# Page11_BOOT_CFG.net
KiCad netlist of a schematic drawn in Altium Designer
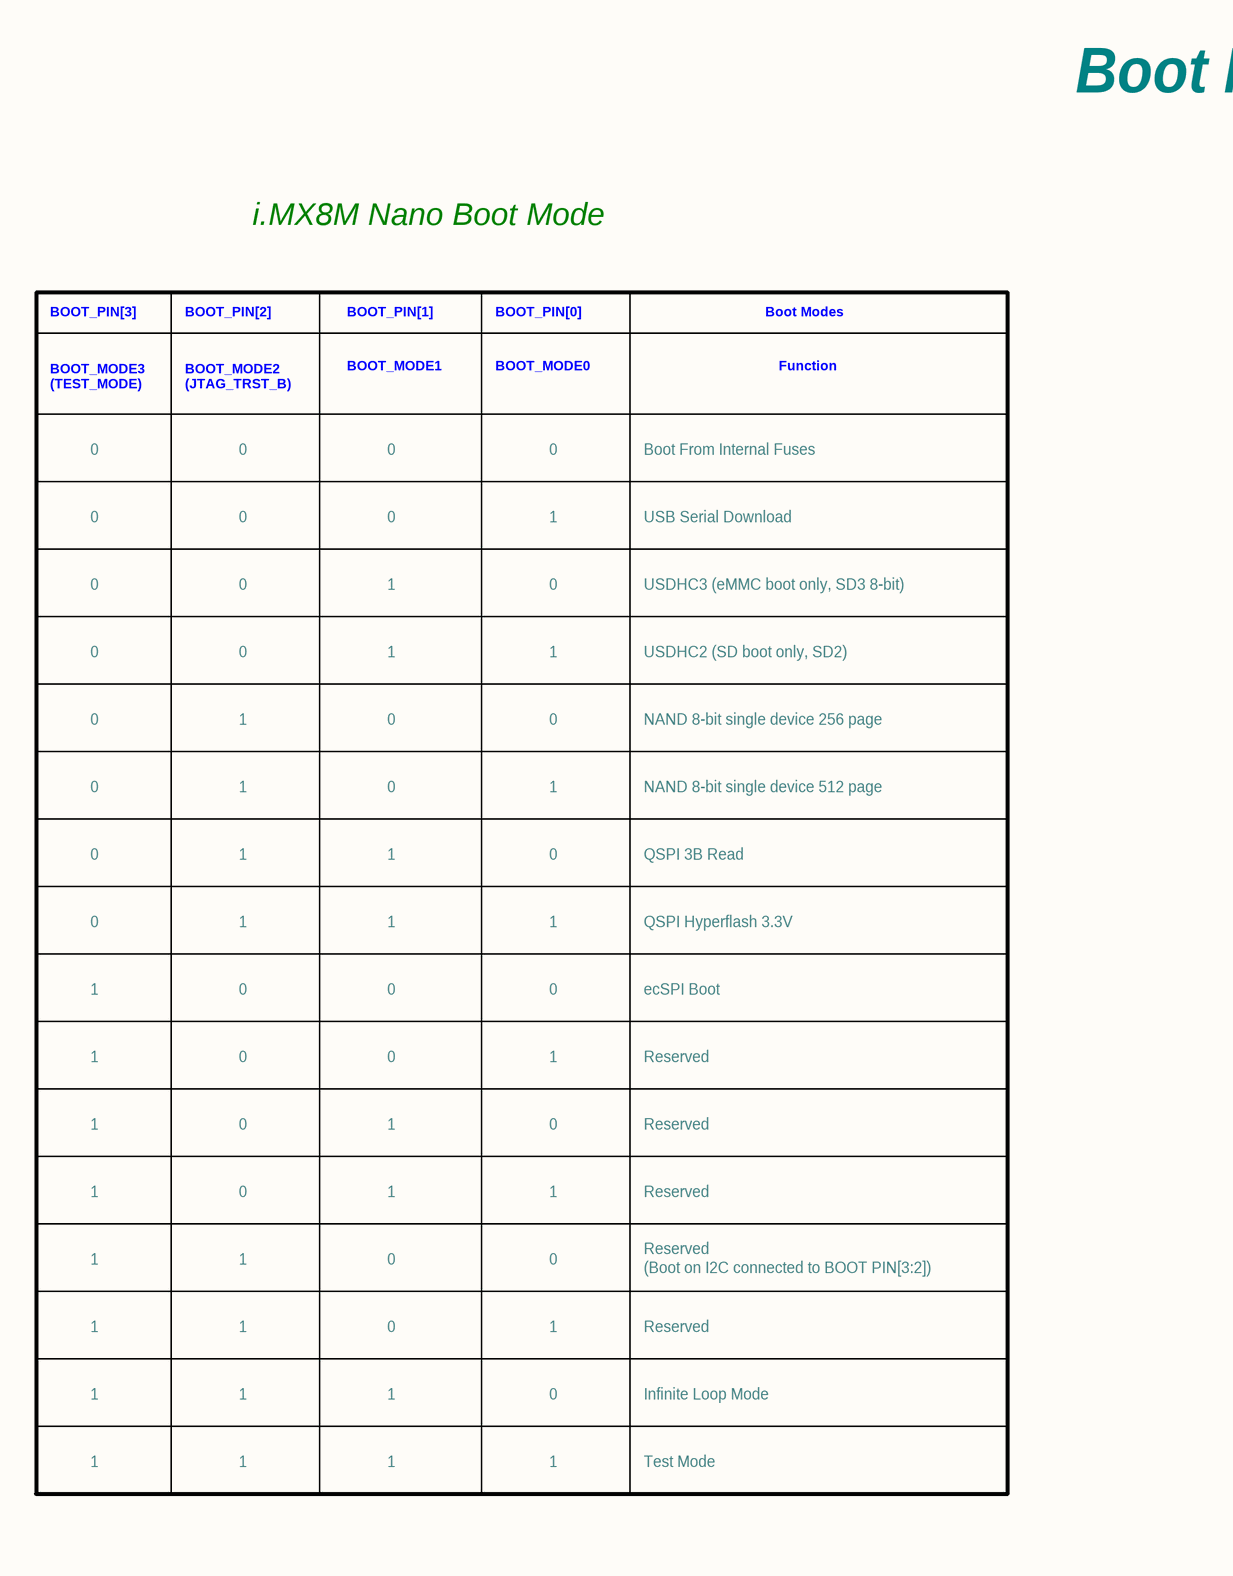
[diagram p0: Page11 BOOT_CFG.SchDoc, left]
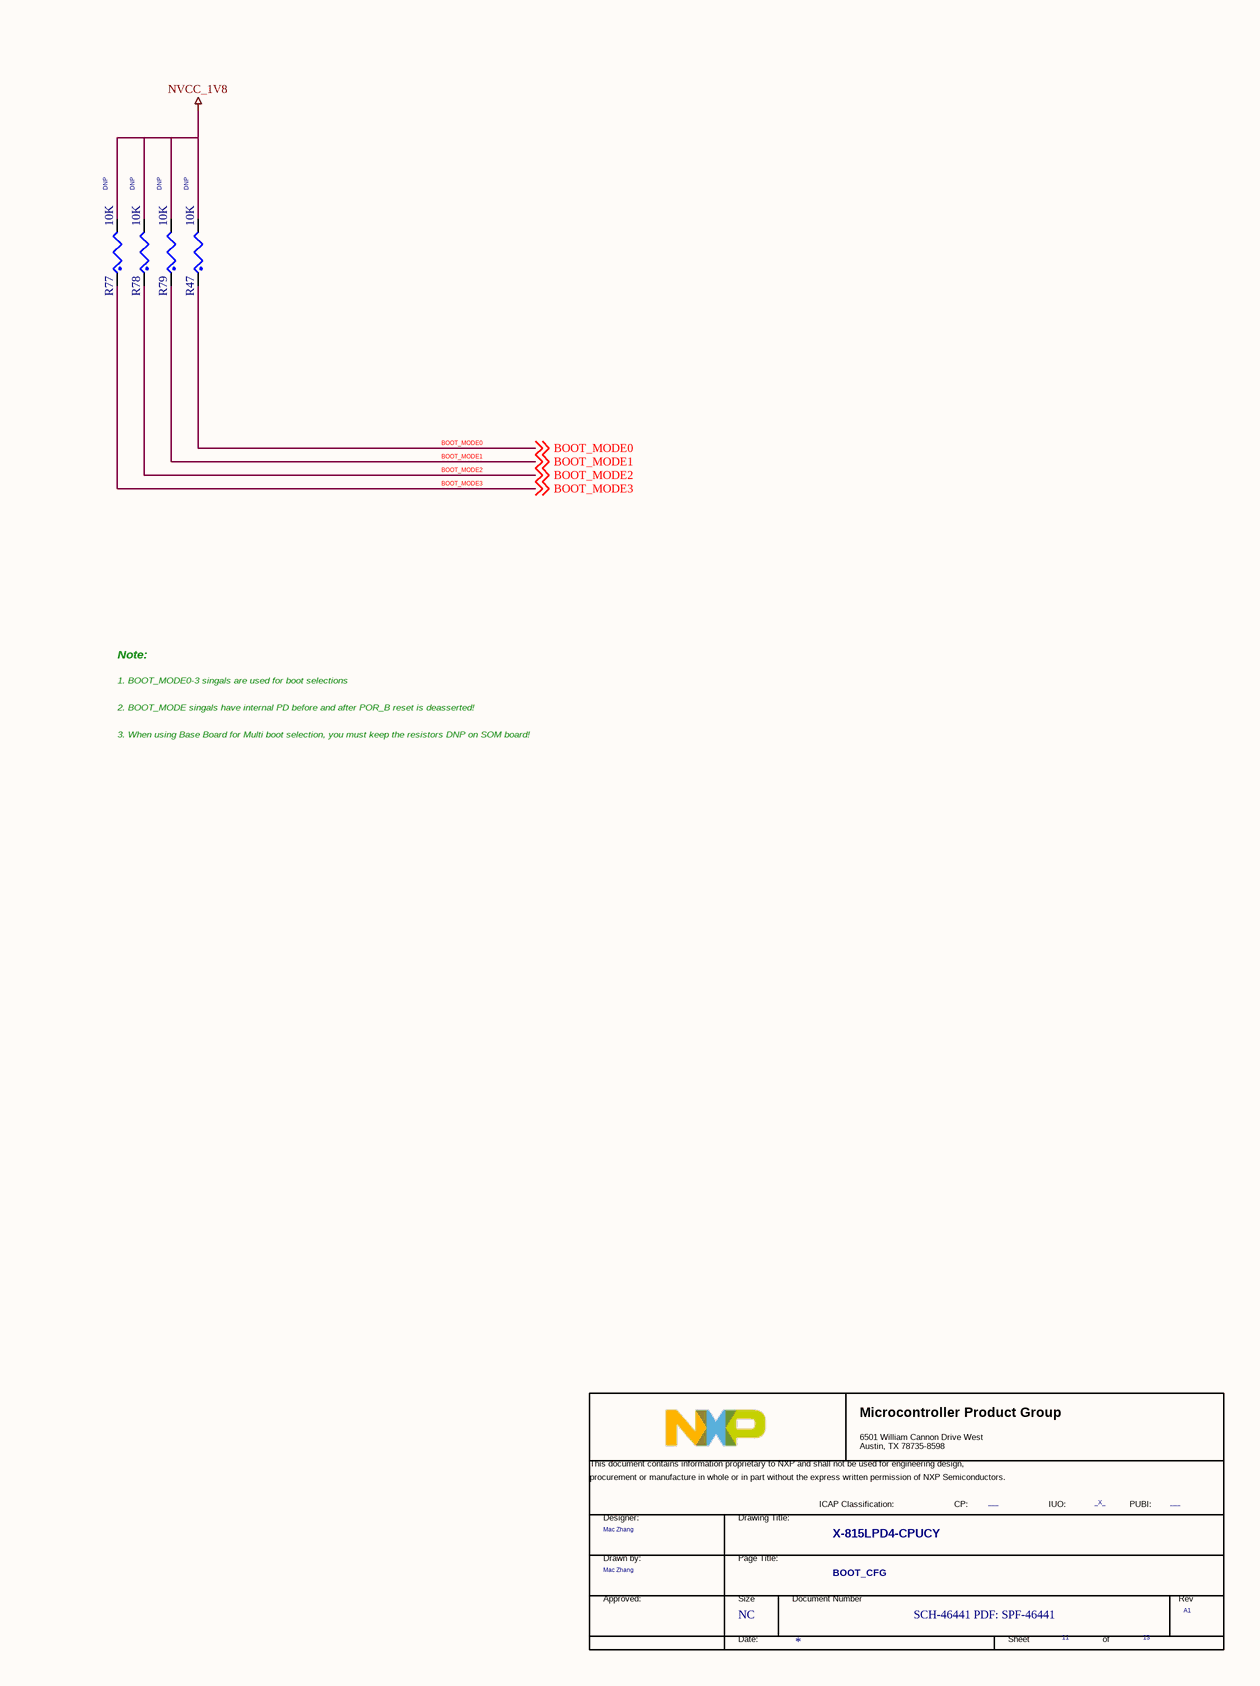
[diagram p1: Page11 BOOT_CFG.SchDoc, right]

(export (version "E")
  (design (tool "Eeschema 10.0.6"))
  (components
    (comp (ref "*")
      (value "TitleBlock_MCPG")
      (fields
        (field (name "DOC") "SCH-46441 PDF: SPF-46441")
        (field (name "REVCODE") "A1")
        (field (name "TITLE") "X-815LPD4-CPUCY")
        (field (name "PAGE SIZE") "NC")
        (field (name "PAGE NUMBER") "11")
        (field (name "PAGE COUNT") "13")
        (field (name "PAGETITLE") "BOOT_CFG")
        (field (name "DESIGNER") "Mac Zhang")
        (field (name "DRAWNBY") "Mac Zhang")
        (field (name "PUBI") "___")
        (field (name "FIUO") "_X_")
        (field (name "FCP") "___")
      )
      (libsource (lib "*") (part "TitleBlock_MCPG"))
    )
    (comp (ref "R47")
      (value "10K")
      (footprint "0402_CC")
      (description "RES MF 10K 1/16W 5% 0402")
      (fields (field (name "ASSY_OPT") "DNP") (field (name "TOLERANCE") "5%"))
      (libsource (lib "*") (part "RES"))
    )
    (comp (ref "R77")
      (value "10K")
      (footprint "0402_CC")
      (description "RES MF 10K 1/16W 5% 0402")
      (fields (field (name "ASSY_OPT") "DNP") (field (name "TOLERANCE") "5%"))
      (libsource (lib "*") (part "RES"))
    )
    (comp (ref "R78")
      (value "10K")
      (footprint "0402_CC")
      (description "RES MF 10K 1/16W 5% 0402")
      (fields (field (name "ASSY_OPT") "DNP") (field (name "TOLERANCE") "5%"))
      (libsource (lib "*") (part "RES"))
    )
    (comp (ref "R79")
      (value "10K")
      (footprint "0402_CC")
      (description "RES MF 10K 1/16W 5% 0402")
      (fields (field (name "ASSY_OPT") "DNP") (field (name "TOLERANCE") "5%"))
      (libsource (lib "*") (part "RES"))
    )
  )
  (nets
    (net (code "1") (name "BOOT_MODE0") (class "Default")
      (node (ref "R47") (pin "1") (pinfunction "1_1") (pintype "passive"))
    )
    (net (code "2") (name "BOOT_MODE1") (class "Default")
      (node (ref "R79") (pin "1") (pinfunction "1_1") (pintype "passive"))
    )
    (net (code "3") (name "BOOT_MODE2") (class "Default")
      (node (ref "R78") (pin "1") (pinfunction "1_1") (pintype "passive"))
    )
    (net (code "4") (name "BOOT_MODE3") (class "Default")
      (node (ref "R77") (pin "1") (pinfunction "1_1") (pintype "passive"))
    )
    (net (code "5") (name "NVCC_1V8") (class "Default")
      (node (ref "R47") (pin "2") (pinfunction "2_2") (pintype "passive"))
      (node (ref "R77") (pin "2") (pinfunction "2_2") (pintype "passive"))
      (node (ref "R78") (pin "2") (pinfunction "2_2") (pintype "passive"))
      (node (ref "R79") (pin "2") (pinfunction "2_2") (pintype "passive"))
    )
  )
)
